# 02_-_DCDC__5V7.net
KiCad netlist of a schematic drawn in Altium Designer
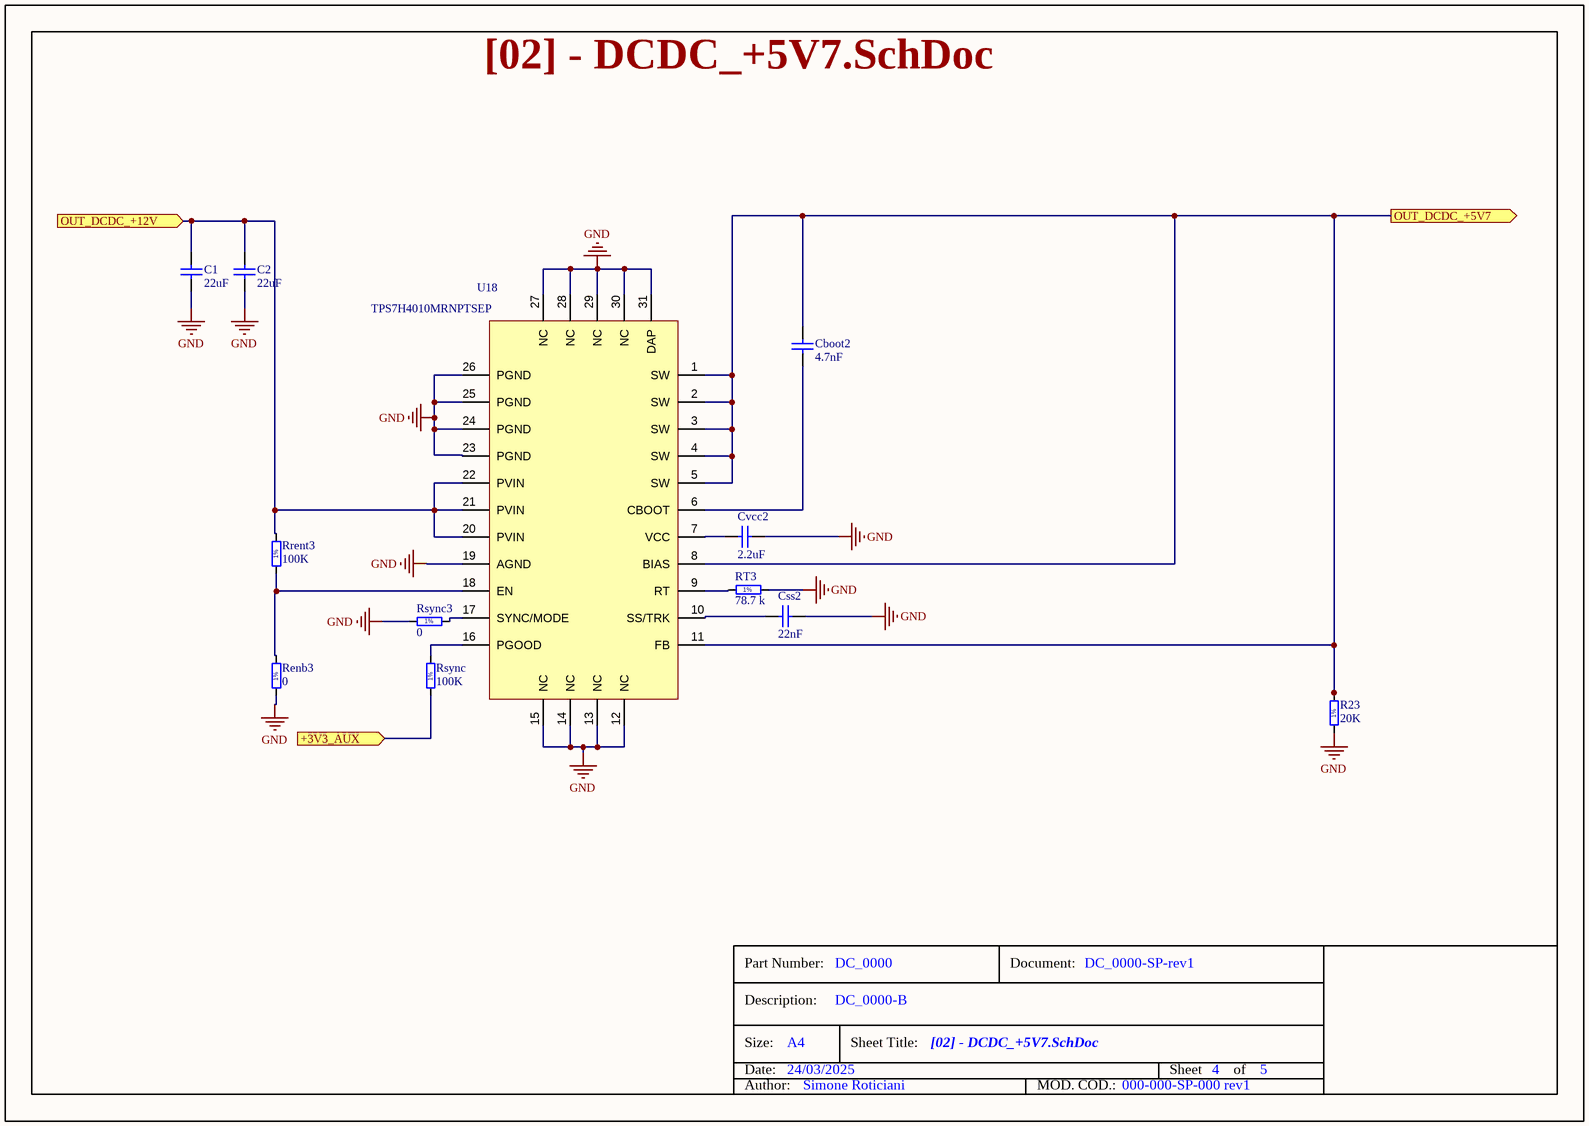
[diagram p0: [02] - DCDC_+5V7.SchDoc]

(export (version "E")
  (design (tool "Eeschema 10.0.6"))
  (components
    (comp (ref "C1")
      (value "22uF")
      (footprint "CAPC320X160X180L55N")
      (description "CAP CER 22uF 25V ±20% X7S 1206")
      (fields
        (field (name "MANUFACTURER") "Murata")
        (field (name "MANUFACTURER PART NUMBER") "GRM31CC71E226ME15L")
      )
      (libsource (lib "W_Passive") (part "GRM31CC71E226ME15L"))
    )
    (comp (ref "C2")
      (value "22uF")
      (footprint "CAPC320X160X180L55N")
      (description "CAP CER 22uF 25V ±20% X7S 1206")
      (fields
        (field (name "MANUFACTURER") "Murata")
        (field (name "MANUFACTURER PART NUMBER") "GRM31CC71E226ME15L")
      )
      (libsource (lib "W_Passive") (part "GRM31CC71E226ME15L"))
    )
    (comp (ref "Cboot2")
      (value "4.7nF")
      (footprint "CAPC100X55X55L35N")
      (description "0402 4.7 nF 25 V ±10% Tolerance X7R SMT Multilayer Ceramic Capacitor")
      (fields
        (field (name "MANUFACTURER") "Murata")
        (field (name "MANUFACTURER PART NUMBER") "GRM155R71E472KA01D")
      )
      (libsource (lib "W_Passive") (part "GRM155R71E472KA01"))
    )
    (comp (ref "Css2")
      (value "22nF")
      (footprint "CAPC100X55X55L35N")
      (description "Multilayer Ceramic Capacitor, 0.022 uF, 25 V, ± 5%, X7R, 0402 [1005 Metric]")
      (fields
        (field (name "MANUFACTURER") "Murata")
        (field (name "MANUFACTURER PART NUMBER") "GRM155R71E223JA61D")
      )
      (libsource (lib "W_Passive") (part "GRM155R71E223JA61"))
    )
    (comp (ref "Cvcc2")
      (value "2.2uF")
      (footprint "CAPC100X55X55L35N")
      (description "Multilayer Ceramic Capacitor, 2.2 uF, 16 V, ± 20%, X7T, 0402 [1005 Metric]")
      (fields
        (field (name "MANUFACTURER") "Murata")
        (field (name "MANUFACTURER PART NUMBER") "GRM155D71C225ME11D")
      )
      (libsource (lib "W_Passive") (part "GRM155D71C225ME11"))
    )
    (comp (ref "R23")
      (value "20K")
      (footprint "RESC100X50X40L25N")
      (description "RES 20K OHM 1/16W 1% 0402")
      (fields (field (name "TOLERANCE") "±1%") (field (name "MANUFACTURER") "Vishay Dale"))
      (libsource (lib "W_Passive") (part "CRCW040220K0FKED"))
    )
    (comp (ref "Renb3")
      (value "0")
      (footprint "RESC100X50X40L25N")
      (description "RES  100K OHM 1/16W 1% 0402")
      (fields (field (name "TOLERANCE") "±1%") (field (name "MANUFACTURER") "Vishay Dale"))
      (libsource (lib "W_Passive") (part "CRCW0402100KFKED"))
    )
    (comp (ref "Rrent3")
      (value "100K")
      (footprint "RESC100X50X40L25N")
      (description "RES 100K OHM 1/16W 1% 0402")
      (fields (field (name "TOLERANCE") "±1%") (field (name "MANUFACTURER") "Vishay Dale"))
      (libsource (lib "W_Passive") (part "CRCW0402100KFKED"))
    )
    (comp (ref "Rsync")
      (value "100K")
      (footprint "RESC100X50X40L25N")
      (description "RES  100K OHM 1/16W 1% 0402")
      (fields (field (name "TOLERANCE") "±1%") (field (name "MANUFACTURER") "Vishay Dale"))
      (libsource (lib "W_Passive") (part "CRCW0402100KFKED"))
    )
    (comp (ref "Rsync3")
      (value "0")
      (footprint "RESC100X50X40L25N")
      (description "RES  100K OHM 1/16W 1% 0402")
      (fields (field (name "TOLERANCE") "±1%") (field (name "MANUFACTURER") "Vishay Dale"))
      (libsource (lib "W_Passive") (part "CRCW0402100KFKED"))
    )
    (comp (ref "RT3")
      (value "78.7 k")
      (footprint "RESC100X50X40L25N")
      (description "RES 78K7 OHM 1/16W 1% 0402")
      (fields (field (name "TOLERANCE") "±1%") (field (name "MANUFACTURER") "Vishay Dale"))
      (libsource (lib "W_Passive") (part "CRCW040278K7FKED"))
    )
    (comp (ref "U18")
      (value "TPS7H4010MRNPTSEP")
      (footprint "TPS7H4010MRNPTSEP")
      (description "Buck Switching Regulator IC Positive Adjustable 1V 1 Output 6A 30-WFQFN Exposed Pad")
      (fields (field (name "MANUFACTURER") "Texas Instruments"))
      (libsource (lib "W_IC") (part "TPS7H4010MRNPTSEP"))
    )
  )
  (nets
    (net (code "1") (name "/+3V3_AUX") (class "Default")
      (node (ref "Rsync") (pin "1") (pinfunction "1_1") (pintype "passive"))
    )
    (net (code "2") (name "/OUT_DCDC_+5V7") (class "Default")
      (node (ref "Cboot2") (pin "2") (pinfunction "2_2") (pintype "passive"))
      (node (ref "R23") (pin "2") (pinfunction "2_2") (pintype "passive"))
      (node (ref "U18") (pin "1") (pinfunction "SW_1") (pintype "passive"))
      (node (ref "U18") (pin "11") (pinfunction "FB_11") (pintype "passive"))
      (node (ref "U18") (pin "2") (pinfunction "SW_2") (pintype "passive"))
      (node (ref "U18") (pin "3") (pinfunction "SW_3") (pintype "passive"))
      (node (ref "U18") (pin "4") (pinfunction "SW_4") (pintype "passive"))
      (node (ref "U18") (pin "5") (pinfunction "SW_5") (pintype "passive"))
      (node (ref "U18") (pin "8") (pinfunction "BIAS_8") (pintype "passive"))
    )
    (net (code "3") (name "/OUT_DCDC_+12V") (class "Default")
      (node (ref "C1") (pin "2") (pinfunction "2_2") (pintype "passive"))
      (node (ref "C2") (pin "2") (pinfunction "2_2") (pintype "passive"))
      (node (ref "Rrent3") (pin "2") (pinfunction "2_2") (pintype "passive"))
      (node (ref "U18") (pin "20") (pinfunction "PVIN_20") (pintype "passive"))
      (node (ref "U18") (pin "21") (pinfunction "PVIN_21") (pintype "passive"))
      (node (ref "U18") (pin "22") (pinfunction "PVIN_22") (pintype "passive"))
    )
    (net (code "4") (name "GND") (class "Default")
      (node (ref "C1") (pin "1") (pinfunction "1_1") (pintype "passive"))
      (node (ref "C2") (pin "1") (pinfunction "1_1") (pintype "passive"))
      (node (ref "Css2") (pin "2") (pinfunction "2_2") (pintype "passive"))
      (node (ref "Cvcc2") (pin "2") (pinfunction "2_2") (pintype "passive"))
      (node (ref "R23") (pin "1") (pinfunction "1_1") (pintype "passive"))
      (node (ref "RT3") (pin "2") (pinfunction "2_2") (pintype "passive"))
      (node (ref "Renb3") (pin "1") (pinfunction "1_1") (pintype "passive"))
      (node (ref "Rsync3") (pin "1") (pinfunction "1_1") (pintype "passive"))
      (node (ref "U18") (pin "12") (pinfunction "NC_12") (pintype "passive"))
      (node (ref "U18") (pin "13") (pinfunction "NC_13") (pintype "passive"))
      (node (ref "U18") (pin "14") (pinfunction "NC_14") (pintype "passive"))
      (node (ref "U18") (pin "15") (pinfunction "NC_15") (pintype "passive"))
      (node (ref "U18") (pin "19") (pinfunction "AGND_19") (pintype "passive"))
      (node (ref "U18") (pin "23") (pinfunction "PGND_23") (pintype "passive"))
      (node (ref "U18") (pin "24") (pinfunction "PGND_24") (pintype "passive"))
      (node (ref "U18") (pin "25") (pinfunction "PGND_25") (pintype "passive"))
      (node (ref "U18") (pin "26") (pinfunction "PGND_26") (pintype "passive"))
      (node (ref "U18") (pin "27") (pinfunction "NC_27") (pintype "passive"))
      (node (ref "U18") (pin "28") (pinfunction "NC_28") (pintype "passive"))
      (node (ref "U18") (pin "29") (pinfunction "NC_29") (pintype "passive"))
      (node (ref "U18") (pin "30") (pinfunction "NC_30") (pintype "passive"))
      (node (ref "U18") (pin "31") (pinfunction "DAP_31") (pintype "passive"))
    )
    (net (code "5") (name "Net-(U18-CBOOT)") (class "Default")
      (node (ref "Cboot2") (pin "1") (pinfunction "1_1") (pintype "passive"))
      (node (ref "U18") (pin "6") (pinfunction "CBOOT_6") (pintype "passive"))
    )
    (net (code "6") (name "Net-(U18-EN)") (class "Default")
      (node (ref "Renb3") (pin "2") (pinfunction "2_2") (pintype "passive"))
      (node (ref "Rrent3") (pin "1") (pinfunction "1_1") (pintype "passive"))
      (node (ref "U18") (pin "18") (pinfunction "EN_18") (pintype "passive"))
    )
    (net (code "7") (name "Net-(U18-PGOOD)") (class "Default")
      (node (ref "Rsync") (pin "2") (pinfunction "2_2") (pintype "passive"))
      (node (ref "U18") (pin "16") (pinfunction "PGOOD_16") (pintype "passive"))
    )
    (net (code "8") (name "Net-(U18-RT)") (class "Default")
      (node (ref "RT3") (pin "1") (pinfunction "1_1") (pintype "passive"))
      (node (ref "U18") (pin "9") (pinfunction "RT_9") (pintype "passive"))
    )
    (net (code "9") (name "Net-(U18-SS{slash}TRK)") (class "Default")
      (node (ref "Css2") (pin "1") (pinfunction "1_1") (pintype "passive"))
      (node (ref "U18") (pin "10") (pinfunction "SS/TRK_10") (pintype "passive"))
    )
    (net (code "10") (name "Net-(U18-SYNC{slash}MODE)") (class "Default")
      (node (ref "Rsync3") (pin "2") (pinfunction "2_2") (pintype "passive"))
      (node (ref "U18") (pin "17") (pinfunction "SYNC/MODE_17") (pintype "passive"))
    )
    (net (code "11") (name "Net-(U18-VCC)") (class "Default")
      (node (ref "Cvcc2") (pin "1") (pinfunction "1_1") (pintype "passive"))
      (node (ref "U18") (pin "7") (pinfunction "VCC_7") (pintype "passive"))
    )
  )
)
